# voltage_sense.net
KiCad netlist of a schematic drawn in Altium Designer
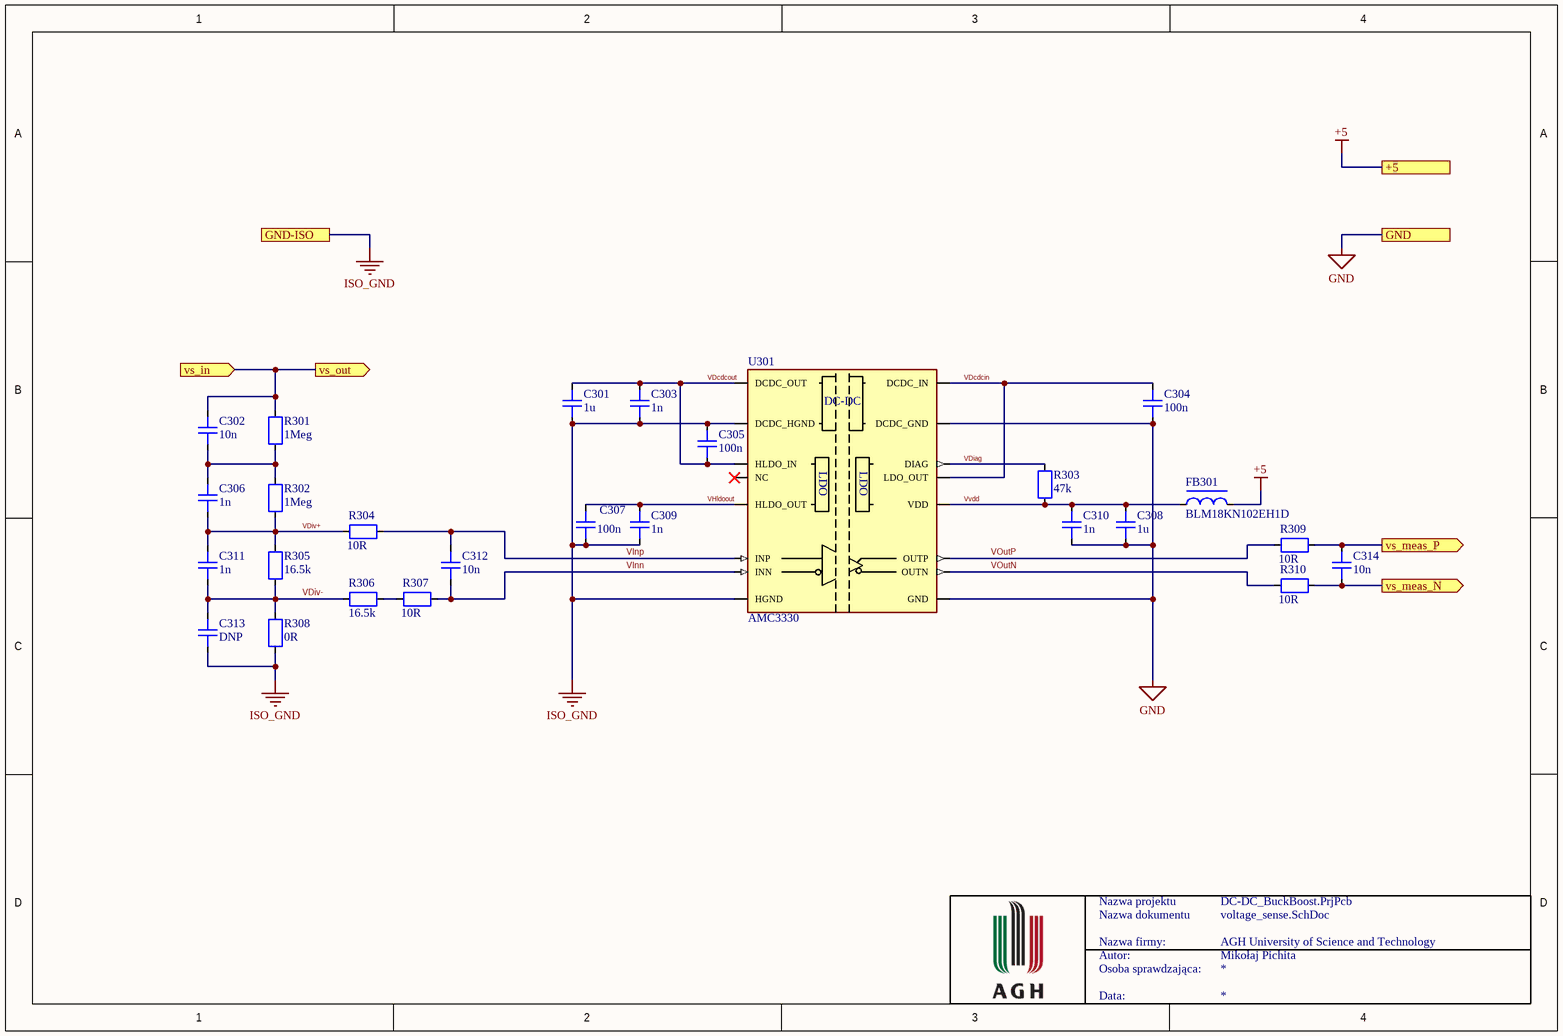
[diagram p0: voltage_sense.SchDoc]

(export (version "E")
  (design (tool "Eeschema 10.0.6"))
  (components
    (comp (ref "C301")
      (value "1u")
      (footprint "CAP1206")
      (libsource (lib "schematic_library") (part "Capacitor"))
    )
    (comp (ref "C302")
      (value "10n")
      (footprint "CAP0603")
      (libsource (lib "schematic_library") (part "Capacitor"))
    )
    (comp (ref "C303")
      (value "1n")
      (footprint "CAP0603")
      (libsource (lib "schematic_library") (part "Capacitor"))
    )
    (comp (ref "C304")
      (value "100n")
      (footprint "CAP0603")
      (libsource (lib "schematic_library") (part "Capacitor"))
    )
    (comp (ref "C305")
      (value "100n")
      (footprint "CAP0603")
      (libsource (lib "schematic_library") (part "Capacitor"))
    )
    (comp (ref "C306")
      (value "1n")
      (footprint "CAP0603")
      (libsource (lib "schematic_library") (part "Capacitor"))
    )
    (comp (ref "C307")
      (value "100n")
      (footprint "CAP0603")
      (libsource (lib "schematic_library") (part "Capacitor"))
    )
    (comp (ref "C308")
      (value "1u")
      (footprint "CAP1206")
      (libsource (lib "schematic_library") (part "Capacitor"))
    )
    (comp (ref "C309")
      (value "1n")
      (footprint "CAP0603")
      (libsource (lib "schematic_library") (part "Capacitor"))
    )
    (comp (ref "C310")
      (value "1n")
      (footprint "CAP1206")
      (libsource (lib "schematic_library") (part "Capacitor"))
    )
    (comp (ref "C311")
      (value "1n")
      (footprint "CAP0603")
      (libsource (lib "schematic_library") (part "Capacitor"))
    )
    (comp (ref "C312")
      (value "10n")
      (footprint "CAP0603")
      (libsource (lib "schematic_library") (part "Capacitor"))
    )
    (comp (ref "C313")
      (value "DNP")
      (footprint "CAP0603")
      (libsource (lib "schematic_library") (part "Capacitor"))
    )
    (comp (ref "C314")
      (value "10n")
      (footprint "CAP0603")
      (libsource (lib "schematic_library") (part "Capacitor"))
    )
    (comp (ref "FB301")
      (value "BLM18KN102EH1D")
      (footprint "RES0603")
      (libsource (lib "schematic_library") (part "Ferrite Bead"))
    )
    (comp (ref "R301")
      (value "1Meg")
      (footprint "RES0603")
      (libsource (lib "schematic_library") (part "Resistor"))
    )
    (comp (ref "R302")
      (value "1Meg")
      (footprint "RES0603")
      (libsource (lib "schematic_library") (part "Resistor"))
    )
    (comp (ref "R303")
      (value "47k")
      (footprint "RES0603")
      (libsource (lib "schematic_library") (part "Resistor"))
    )
    (comp (ref "R304")
      (value "10R")
      (footprint "RES0603")
      (libsource (lib "schematic_library") (part "Resistor"))
    )
    (comp (ref "R305")
      (value "16.5k")
      (footprint "RES0603")
      (libsource (lib "schematic_library") (part "Resistor"))
    )
    (comp (ref "R306")
      (value "16.5k")
      (footprint "RES0603")
      (libsource (lib "schematic_library") (part "Resistor"))
    )
    (comp (ref "R307")
      (value "10R")
      (footprint "RES0603")
      (libsource (lib "schematic_library") (part "Resistor"))
    )
    (comp (ref "R308")
      (value "0R")
      (footprint "RES0603")
      (libsource (lib "schematic_library") (part "Resistor"))
    )
    (comp (ref "R309")
      (value "10R")
      (footprint "RES0603")
      (libsource (lib "schematic_library") (part "Resistor"))
    )
    (comp (ref "R310")
      (value "10R")
      (footprint "RES0603")
      (libsource (lib "schematic_library") (part "Resistor"))
    )
    (comp (ref "U301")
      (value "AMC3330")
      (footprint "SOIC127P1030X265-16N")
      (description "±1-V input, precision voltage sensing reinforced isolated amplifier with integrated DC/DC")
      (libsource (lib "schematic_library") (part "AMC3330"))
    )
  )
  (nets
    (net (code "1") (name "+5") (class "Default") (node (ref "FB301") (pin "1") (pintype "passive")))
    (net (code "2") (name "/VDcdcin") (class "Default")
      (node (ref "C304") (pin "1") (pintype "passive"))
      (node (ref "U301") (pin "13") (pinfunction "LDO_OUT_13") (pintype "power_in"))
      (node (ref "U301") (pin "16") (pinfunction "DCDC_IN_16") (pintype "power_in"))
    )
    (net (code "3") (name "/VDcdcout") (class "Default")
      (node (ref "C301") (pin "1") (pintype "passive"))
      (node (ref "C303") (pin "1") (pintype "passive"))
      (node (ref "C305") (pin "2") (pintype "passive"))
      (node (ref "U301") (pin "1") (pinfunction "DCDC_OUT_1") (pintype "power_in"))
      (node (ref "U301") (pin "3") (pinfunction "HLDO_IN_3") (pintype "power_in"))
    )
    (net (code "4") (name "/VDiag") (class "Default")
      (node (ref "R303") (pin "1") (pintype "passive"))
      (node (ref "U301") (pin "14") (pinfunction "DIAG_14") (pintype "output"))
    )
    (net (code "5") (name "/VDiv+") (class "Default")
      (node (ref "C306") (pin "2") (pintype "passive"))
      (node (ref "C311") (pin "1") (pintype "passive"))
      (node (ref "R302") (pin "2") (pintype "passive"))
      (node (ref "R304") (pin "2") (pintype "passive"))
      (node (ref "R305") (pin "1") (pintype "passive"))
    )
    (net (code "6") (name "/VDiv-") (class "Default")
      (node (ref "C311") (pin "2") (pintype "passive"))
      (node (ref "C313") (pin "1") (pintype "passive"))
      (node (ref "R305") (pin "2") (pintype "passive"))
      (node (ref "R306") (pin "1") (pintype "passive"))
      (node (ref "R308") (pin "1") (pintype "passive"))
    )
    (net (code "7") (name "/VHldoout") (class "Default")
      (node (ref "C307") (pin "1") (pintype "passive"))
      (node (ref "C309") (pin "1") (pintype "passive"))
      (node (ref "U301") (pin "5") (pinfunction "HLDO_OUT_5") (pintype "power_in"))
    )
    (net (code "8") (name "/VInn") (class "Default")
      (node (ref "C312") (pin "1") (pintype "passive"))
      (node (ref "R307") (pin "1") (pintype "passive"))
      (node (ref "U301") (pin "7") (pinfunction "INN_7") (pintype "input"))
    )
    (net (code "9") (name "/VInp") (class "Default")
      (node (ref "C312") (pin "2") (pintype "passive"))
      (node (ref "R304") (pin "1") (pintype "passive"))
      (node (ref "U301") (pin "6") (pinfunction "INP_6") (pintype "input"))
    )
    (net (code "10") (name "/VOutN") (class "Default")
      (node (ref "R310") (pin "2") (pintype "passive"))
      (node (ref "U301") (pin "10") (pinfunction "OUTN_10") (pintype "output"))
    )
    (net (code "11") (name "/VOutP") (class "Default")
      (node (ref "R309") (pin "2") (pintype "passive"))
      (node (ref "U301") (pin "11") (pinfunction "OUTP_11") (pintype "output"))
    )
    (net (code "12") (name "/Vvdd") (class "Default")
      (node (ref "C308") (pin "1") (pintype "passive"))
      (node (ref "C310") (pin "1") (pintype "passive"))
      (node (ref "FB301") (pin "2") (pintype "passive"))
      (node (ref "R303") (pin "2") (pintype "passive"))
      (node (ref "U301") (pin "12") (pinfunction "VDD_12") (pintype "power_in"))
    )
    (net (code "13") (name "/vs_in") (class "Default")
      (node (ref "C302") (pin "1") (pintype "passive"))
      (node (ref "R301") (pin "1") (pintype "passive"))
    )
    (net (code "14") (name "/vs_meas_N") (class "Default")
      (node (ref "C314") (pin "1") (pintype "passive"))
      (node (ref "R310") (pin "1") (pintype "passive"))
    )
    (net (code "15") (name "/vs_meas_P") (class "Default")
      (node (ref "C314") (pin "2") (pintype "passive"))
      (node (ref "R309") (pin "1") (pintype "passive"))
    )
    (net (code "16") (name "GND") (class "Default")
      (node (ref "C304") (pin "2") (pintype "passive"))
      (node (ref "C308") (pin "2") (pintype "passive"))
      (node (ref "C310") (pin "2") (pintype "passive"))
      (node (ref "U301") (pin "15") (pinfunction "DCDC_GND_15") (pintype "power_in"))
      (node (ref "U301") (pin "9") (pinfunction "GND_9") (pintype "power_in"))
    )
    (net (code "17") (name "ISO_GND") (class "Default")
      (node (ref "C301") (pin "2") (pintype "passive"))
      (node (ref "C303") (pin "2") (pintype "passive"))
      (node (ref "C305") (pin "1") (pintype "passive"))
      (node (ref "C307") (pin "2") (pintype "passive"))
      (node (ref "C309") (pin "2") (pintype "passive"))
      (node (ref "C313") (pin "2") (pintype "passive"))
      (node (ref "R308") (pin "2") (pintype "passive"))
      (node (ref "U301") (pin "2") (pinfunction "DCDC_HGND_2") (pintype "power_in"))
      (node (ref "U301") (pin "8") (pinfunction "HGND_8") (pintype "power_in"))
    )
    (net (code "18") (name "Net-(C302-Pad2)") (class "Default")
      (node (ref "C302") (pin "2") (pintype "passive"))
      (node (ref "C306") (pin "1") (pintype "passive"))
      (node (ref "R301") (pin "2") (pintype "passive"))
      (node (ref "R302") (pin "1") (pintype "passive"))
    )
    (net (code "19") (name "Net-(R306-Pad2)") (class "Default")
      (node (ref "R306") (pin "2") (pintype "passive"))
      (node (ref "R307") (pin "2") (pintype "passive"))
    )
    (net (code "20") (name "unconnected-(U301-NC-Pad4)") (class "Default")
      (node (ref "U301") (pin "4") (pinfunction "NC_4") (pintype "passive+no_connect"))
    )
  )
)
